# QRE1113_breakout_schmitt.net
KiCad netlist of a schematic drawn in EAGLE
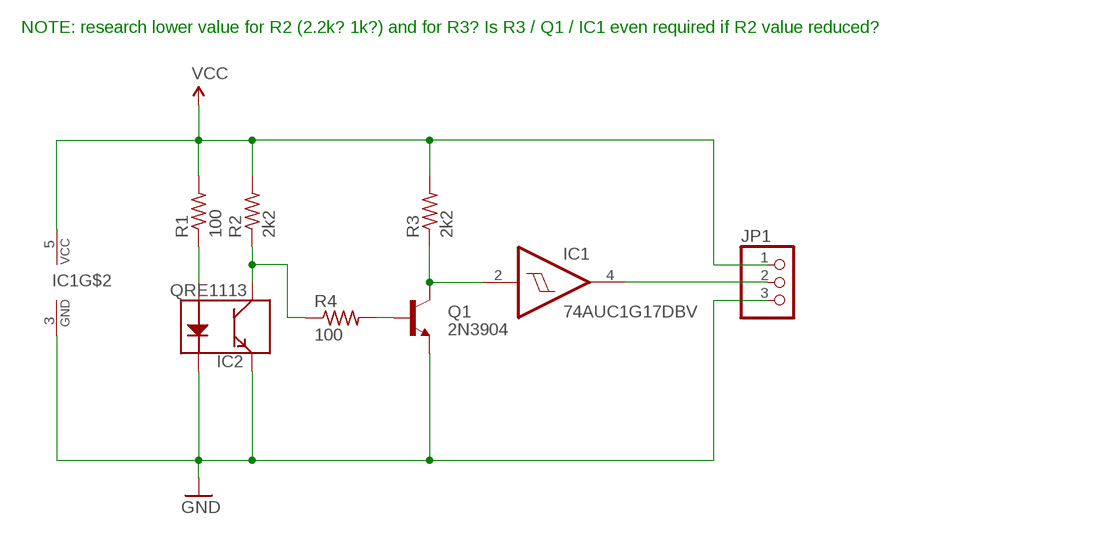
[diagram p0: schematic, sheet 1]

(export (version "E")
  (design (tool "Eeschema 10.0.6"))
  (components
    (comp (ref "IC1")
      (value "74AUC1G17DBV")
      (footprint "eagle-import:SOT23-5")
      (libsource (lib "eagle-import") (part "741G17DBVAUC"))
    )
    (comp (ref "IC2")
      (value "QRE1113")
      (footprint "eagle-import:QRE1113")
      (libsource (lib "eagle-import") (part "QRE1113"))
    )
    (comp (ref "JP1")
      (value "PINHD-1X03_2.54-S")
      (footprint "eagle-import:1X03-S")
      (libsource (lib "eagle-import") (part "PINHD-1X03_2.54-S"))
    )
    (comp (ref "Q1")
      (value "2N3904")
      (footprint "eagle-import:SOT-23")
      (libsource (lib "eagle-import") (part "2N3904SMD"))
    )
    (comp (ref "R1")
      (value "100")
      (footprint "eagle-import:R0603")
      (libsource (lib "eagle-import") (part "R-US_R0603"))
    )
    (comp (ref "R2")
      (value "2k2")
      (footprint "eagle-import:R0603")
      (libsource (lib "eagle-import") (part "R-US_R0603"))
    )
    (comp (ref "R3")
      (value "2k2")
      (footprint "eagle-import:R0603")
      (libsource (lib "eagle-import") (part "R-US_R0603"))
    )
    (comp (ref "R4")
      (value "100")
      (footprint "eagle-import:R0603")
      (libsource (lib "eagle-import") (part "R-US_R0603"))
    )
  )
  (nets
    (net (code "1") (name "GND") (class "Default")
      (node (ref "IC1") (pin "3") (pinfunction "GND_3") (pintype "power_in"))
      (node (ref "IC2") (pin "2") (pinfunction "K_2") (pintype "bidirectional"))
      (node (ref "IC2") (pin "4") (pinfunction "E_4") (pintype "bidirectional"))
      (node (ref "JP1") (pin "3") (pinfunction "3_3") (pintype "passive"))
      (node (ref "Q1") (pin "2") (pinfunction "E_2") (pintype "passive"))
    )
    (net (code "2") (name "Net-(IC1A-I)") (class "Default")
      (node (ref "IC1") (pin "2") (pinfunction "I_2") (pintype "input"))
      (node (ref "Q1") (pin "1") (pinfunction "C_1") (pintype "passive"))
      (node (ref "R3") (pin "1") (pinfunction "1_1") (pintype "passive"))
    )
    (net (code "3") (name "Net-(IC1A-O)") (class "Default")
      (node (ref "IC1") (pin "4") (pinfunction "O_4") (pintype "output"))
      (node (ref "JP1") (pin "2") (pinfunction "2_2") (pintype "passive"))
    )
    (net (code "4") (name "Net-(IC2-A)") (class "Default")
      (node (ref "IC2") (pin "1") (pinfunction "A_1") (pintype "bidirectional"))
      (node (ref "R1") (pin "1") (pinfunction "1_1") (pintype "passive"))
    )
    (net (code "5") (name "Net-(IC2-C)") (class "Default")
      (node (ref "IC2") (pin "3") (pinfunction "C_3") (pintype "bidirectional"))
      (node (ref "R2") (pin "1") (pinfunction "1_1") (pintype "passive"))
      (node (ref "R4") (pin "1") (pinfunction "1_1") (pintype "passive"))
    )
    (net (code "6") (name "Net-(Q1-B)") (class "Default")
      (node (ref "Q1") (pin "3") (pinfunction "B_3") (pintype "passive"))
      (node (ref "R4") (pin "2") (pinfunction "2_2") (pintype "passive"))
    )
    (net (code "7") (name "VCC") (class "Default")
      (node (ref "IC1") (pin "5") (pinfunction "VCC_5") (pintype "power_in"))
      (node (ref "JP1") (pin "1") (pinfunction "1_1") (pintype "passive"))
      (node (ref "R1") (pin "2") (pinfunction "2_2") (pintype "passive"))
      (node (ref "R2") (pin "2") (pinfunction "2_2") (pintype "passive"))
      (node (ref "R3") (pin "2") (pinfunction "2_2") (pintype "passive"))
    )
  )
)
